# MCU.net
KiCad netlist of a schematic drawn in Altium Designer
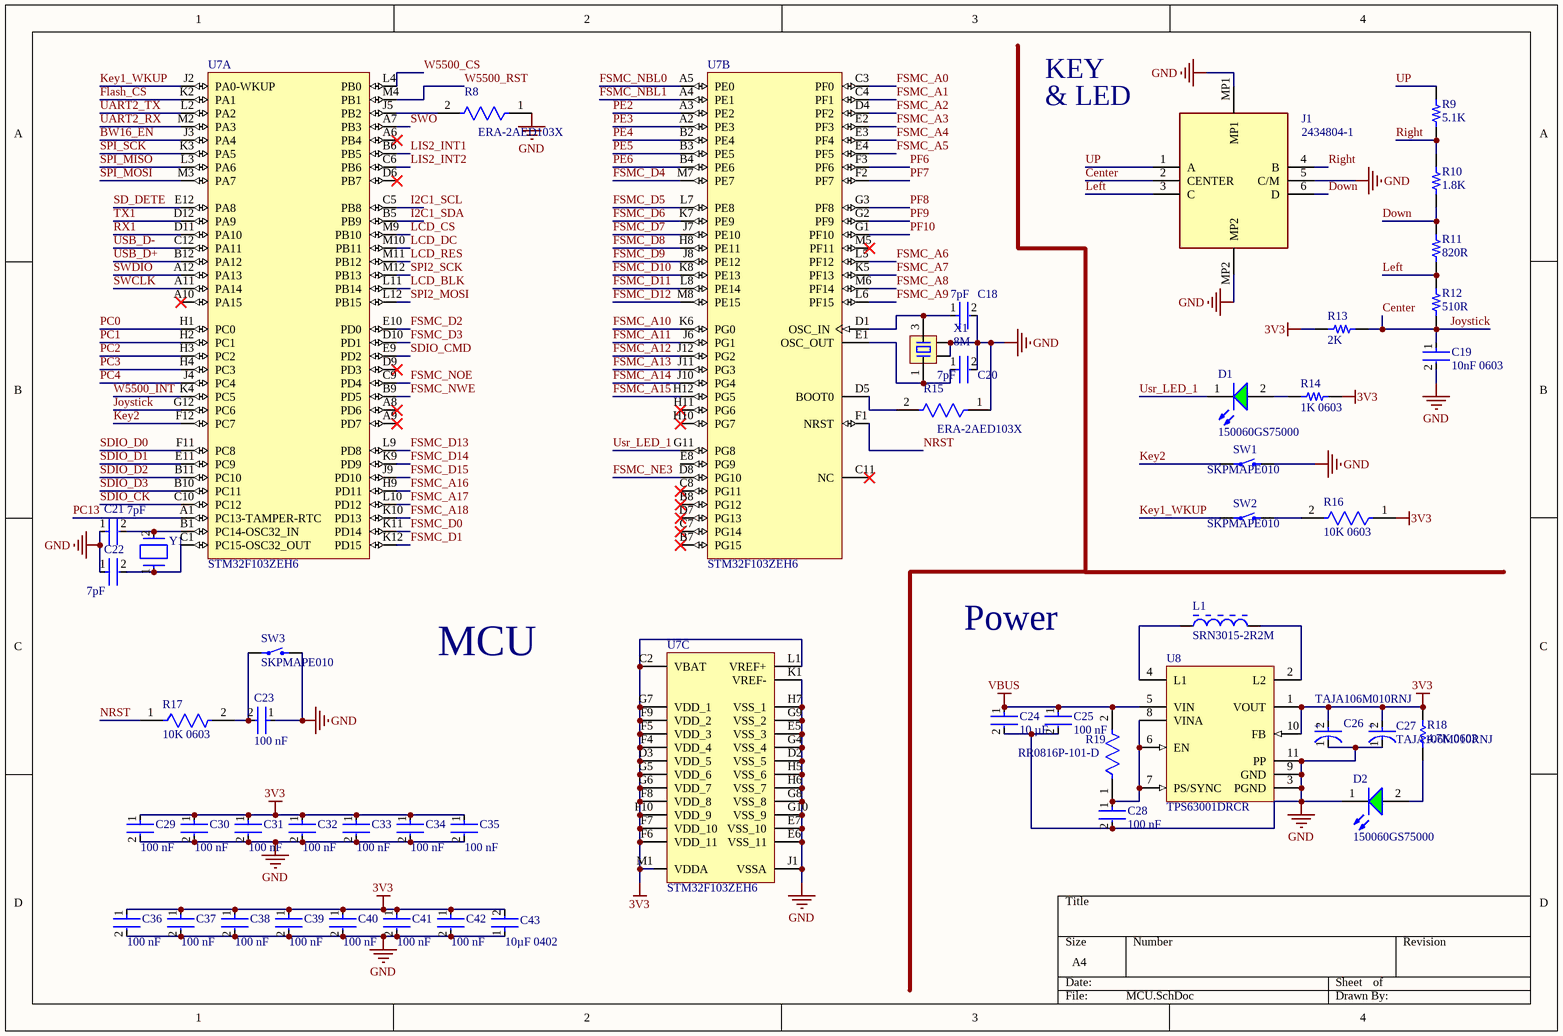
[diagram p0: MCU.SchDoc]

(export (version "E")
  (design (tool "Eeschema 10.0.6"))
  (components
    (comp (ref "C18")
      (value "7pF")
      (footprint "FP-GJM155-0_05-IPC_B")
      (description "Multi-Layer Ceramic Capacitor 7pF C0G  ±0.5pF 0402 Paper T/R")
      (libsource (lib "Altium Content Vault") (part "02cd4be3c70576c341d710602a673aa"))
    )
    (comp (ref "C19")
      (value "10nF 0603")
      (footprint "FP-CC0603-DA-MFG")
      (description "CAP CER 10000PF 50V X7R 0603")
      (fields (field (name "TOLERANCE") "0.1") (field (name "MANUFACTURER PART NUMBER") "CC0603KRX7R9BB103"))
      (libsource (lib "Altium Content Vault") (part "11868f565c42a9108669ba33697ecf6"))
    )
    (comp (ref "C20")
      (value "7pF")
      (footprint "FP-GJM155-0_05-IPC_B")
      (description "Multi-Layer Ceramic Capacitor 7pF C0G  ±0.5pF 0402 Paper T/R")
      (libsource (lib "Altium Content Vault") (part "02cd4be3c70576c341d710602a673aa"))
    )
    (comp (ref "C21")
      (value "7pF")
      (footprint "FP-GJM155-0_05-IPC_B")
      (description "Multi-Layer Ceramic Capacitor 7pF C0G  ±0.5pF 0402 Paper T/R")
      (libsource (lib "Altium Content Vault") (part "02cd4be3c70576c341d710602a673aa"))
    )
    (comp (ref "C22")
      (value "7pF")
      (footprint "FP-GJM155-0_05-IPC_B")
      (description "Multi-Layer Ceramic Capacitor 7pF C0G  ±0.5pF 0402 Paper T/R")
      (libsource (lib "Altium Content Vault") (part "02cd4be3c70576c341d710602a673aa"))
    )
    (comp (ref "C23")
      (value "100 nF")
      (footprint "FP-CL10-IPC_A")
      (description "Cap Ceramic 100nF 100V X7R ±10% Pad SMD 0603 +125°C T/R")
      (fields (field (name "TOLERANCE") "10%"))
      (libsource (lib "Altium Content Vault") (part "b4654b650e69147ec39a6b967a45e02"))
    )
    (comp (ref "C24")
      (value "10 µF")
      (footprint "FP-CL10-IPC_C")
      (description "Cap Ceramic 10uF 25V X5R ±20% Pad SMD 0603 +85°C T/R")
      (fields (field (name "TOLERANCE") "20%"))
      (libsource (lib "Altium Content Vault") (part "b4654b650e69147ec39a6b967a45e02"))
    )
    (comp (ref "C25")
      (value "100 nF")
      (footprint "FP-CL10-IPC_A")
      (description "Cap Ceramic 100nF 100V X7R ±10% Pad SMD 0603 +125°C T/R")
      (fields (field (name "TOLERANCE") "10%"))
      (libsource (lib "Altium Content Vault") (part "b4654b650e69147ec39a6b967a45e02"))
    )
    (comp (ref "C26")
      (value "TAJA106M010RNJ")
      (footprint "FP-TAJA-MFG")
      (description "10uF 10V  ±20% 3Ω 1206  SMD Tantalum Capacitor")
      (fields (field (name "TOLERANCE") "20%") (field (name "VOLTAGE") "10V"))
      (libsource (lib "Altium Content Vault") (part "203bc49f2ac43e59fd269a8c329ed05"))
    )
    (comp (ref "C27")
      (value "TAJA106M010RNJ")
      (footprint "FP-TAJA-MFG")
      (description "10uF 10V  ±20% 3Ω 1206  SMD Tantalum Capacitor")
      (fields (field (name "TOLERANCE") "20%") (field (name "VOLTAGE") "10V"))
      (libsource (lib "Altium Content Vault") (part "203bc49f2ac43e59fd269a8c329ed05"))
    )
    (comp (ref "C28")
      (value "100 nF")
      (footprint "FP-CL10-IPC_A")
      (description "Cap Ceramic 100nF 100V X7R ±10% Pad SMD 0603 +125°C T/R")
      (fields (field (name "TOLERANCE") "10%"))
      (libsource (lib "Altium Content Vault") (part "b4654b650e69147ec39a6b967a45e02"))
    )
    (comp (ref "C29")
      (value "100 nF")
      (footprint "FP-C1005-050-0_05-MFG")
      (description "Multilayer Ceramic Capacitors 100nF ±10% 50V X5R SMD 0402")
      (fields (field (name "VOLTAGE") "50V") (field (name "TOLERANCE") "10%"))
      (libsource (lib "Altium Content Vault") (part "b4654b650e69147ec39a6b967a45e02"))
    )
    (comp (ref "C30")
      (value "100 nF")
      (footprint "FP-C1005-050-0_05-MFG")
      (description "Multilayer Ceramic Capacitors 100nF ±10% 50V X5R SMD 0402")
      (fields (field (name "VOLTAGE") "50V") (field (name "TOLERANCE") "10%"))
      (libsource (lib "Altium Content Vault") (part "b4654b650e69147ec39a6b967a45e02"))
    )
    (comp (ref "C31")
      (value "100 nF")
      (footprint "FP-C1005-050-0_05-MFG")
      (description "Multilayer Ceramic Capacitors 100nF ±10% 50V X5R SMD 0402")
      (fields (field (name "VOLTAGE") "50V") (field (name "TOLERANCE") "10%"))
      (libsource (lib "Altium Content Vault") (part "b4654b650e69147ec39a6b967a45e02"))
    )
    (comp (ref "C32")
      (value "100 nF")
      (footprint "FP-C1005-050-0_05-MFG")
      (description "Multilayer Ceramic Capacitors 100nF ±10% 50V X5R SMD 0402")
      (fields (field (name "VOLTAGE") "50V") (field (name "TOLERANCE") "10%"))
      (libsource (lib "Altium Content Vault") (part "b4654b650e69147ec39a6b967a45e02"))
    )
    (comp (ref "C33")
      (value "100 nF")
      (footprint "FP-C1005-050-0_05-MFG")
      (description "Multilayer Ceramic Capacitors 100nF ±10% 50V X5R SMD 0402")
      (fields (field (name "VOLTAGE") "50V") (field (name "TOLERANCE") "10%"))
      (libsource (lib "Altium Content Vault") (part "b4654b650e69147ec39a6b967a45e02"))
    )
    (comp (ref "C34")
      (value "100 nF")
      (footprint "FP-C1005-050-0_05-MFG")
      (description "Multilayer Ceramic Capacitors 100nF ±10% 50V X5R SMD 0402")
      (fields (field (name "VOLTAGE") "50V") (field (name "TOLERANCE") "10%"))
      (libsource (lib "Altium Content Vault") (part "b4654b650e69147ec39a6b967a45e02"))
    )
    (comp (ref "C35")
      (value "100 nF")
      (footprint "FP-C1005-050-0_05-MFG")
      (description "Multilayer Ceramic Capacitors 100nF ±10% 50V X5R SMD 0402")
      (fields (field (name "VOLTAGE") "50V") (field (name "TOLERANCE") "10%"))
      (libsource (lib "Altium Content Vault") (part "b4654b650e69147ec39a6b967a45e02"))
    )
    (comp (ref "C36")
      (value "100 nF")
      (footprint "FP-C1005-050-0_05-MFG")
      (description "Multilayer Ceramic Capacitors 100nF ±10% 50V X5R SMD 0402")
      (fields (field (name "VOLTAGE") "50V") (field (name "TOLERANCE") "10%"))
      (libsource (lib "Altium Content Vault") (part "b4654b650e69147ec39a6b967a45e02"))
    )
    (comp (ref "C37")
      (value "100 nF")
      (footprint "FP-C1005-050-0_05-MFG")
      (description "Multilayer Ceramic Capacitors 100nF ±10% 50V X5R SMD 0402")
      (fields (field (name "VOLTAGE") "50V") (field (name "TOLERANCE") "10%"))
      (libsource (lib "Altium Content Vault") (part "b4654b650e69147ec39a6b967a45e02"))
    )
    (comp (ref "C38")
      (value "100 nF")
      (footprint "FP-C1005-050-0_05-MFG")
      (description "Multilayer Ceramic Capacitors 100nF ±10% 50V X5R SMD 0402")
      (fields (field (name "VOLTAGE") "50V") (field (name "TOLERANCE") "10%"))
      (libsource (lib "Altium Content Vault") (part "b4654b650e69147ec39a6b967a45e02"))
    )
    (comp (ref "C39")
      (value "100 nF")
      (footprint "FP-C1005-050-0_05-MFG")
      (description "Multilayer Ceramic Capacitors 100nF ±10% 50V X5R SMD 0402")
      (fields (field (name "VOLTAGE") "50V") (field (name "TOLERANCE") "10%"))
      (libsource (lib "Altium Content Vault") (part "b4654b650e69147ec39a6b967a45e02"))
    )
    (comp (ref "C40")
      (value "100 nF")
      (footprint "FP-C1005-050-0_05-MFG")
      (description "Multilayer Ceramic Capacitors 100nF ±10% 50V X5R SMD 0402")
      (fields (field (name "VOLTAGE") "50V") (field (name "TOLERANCE") "10%"))
      (libsource (lib "Altium Content Vault") (part "b4654b650e69147ec39a6b967a45e02"))
    )
    (comp (ref "C41")
      (value "100 nF")
      (footprint "FP-C1005-050-0_05-MFG")
      (description "Multilayer Ceramic Capacitors 100nF ±10% 50V X5R SMD 0402")
      (fields (field (name "VOLTAGE") "50V") (field (name "TOLERANCE") "10%"))
      (libsource (lib "Altium Content Vault") (part "b4654b650e69147ec39a6b967a45e02"))
    )
    (comp (ref "C42")
      (value "100 nF")
      (footprint "FP-C1005-050-0_05-MFG")
      (description "Multilayer Ceramic Capacitors 100nF ±10% 50V X5R SMD 0402")
      (fields (field (name "VOLTAGE") "50V") (field (name "TOLERANCE") "10%"))
      (libsource (lib "Altium Content Vault") (part "b4654b650e69147ec39a6b967a45e02"))
    )
    (comp (ref "C43")
      (value "10µF 0402")
      (footprint "FP-CL05A106MP5NUNC-MFG")
      (description "CAP CER 10UF 10V X5R 0402")
      (fields
        (field (name "OCTOPART") "https://octopart.com/cl05a106mp5nunc-samsung-22457395")
        (field (name "TOLERANCE") "20%")
      )
      (libsource (lib "Altium Content Vault") (part "b4654b650e69147ec39a6b967a45e02"))
    )
    (comp (ref "D1")
      (value "150060GS75000")
      (footprint "WL-SMCW_0603_150060xx75000")
      (libsource (lib "Altium Content Vault") (part "LED_Green_2A-1K"))
    )
    (comp (ref "D2")
      (value "150060GS75000")
      (footprint "WL-SMCW_0603_150060xx75000")
      (libsource (lib "Altium Content Vault") (part "LED_Green_2A-1K"))
    )
    (comp (ref "J1")
      (value "2434804-1")
      (footprint "24348041")
      (fields (field (name "MOUSER PART NUMBER") "655-2434804-1"))
      (libsource (lib "Demo") (part "2434804-1"))
    )
    (comp (ref "L1")
      (value "SRN3015-2R2M")
      (footprint "BOUR-SRN3015-2_V")
      (fields (field (name "MANUFACTURER") "Bourns"))
      (libsource (lib "Altium Content Vault") (part "BOUR-IND-2A"))
    )
    (comp (ref "R8")
      (value "ERA-2AED103X")
      (footprint "FP-ERA2A-IPC_B")
      (description "RES SMD 10K OHM 0.5% 1/16W 0402")
      (fields (field (name "TOLERANCE") "0.5%"))
      (libsource (lib "Altium Content Vault") (part "1029c3af85768c4190bb7ad29bc67b5"))
    )
    (comp (ref "R9")
      (value "5.1K")
      (footprint "5.1K_0603")
      (description "SMT Resistor")
      (libsource (lib "Demo") (part "5.1K_0603"))
    )
    (comp (ref "R10")
      (value "1.8K")
      (footprint "5.1K_0603")
      (description "SMT Resistor")
      (libsource (lib "Demo") (part "5.1K_0603"))
    )
    (comp (ref "R11")
      (value "820R")
      (footprint "5.1K_0603")
      (description "SMT Resistor")
      (libsource (lib "Demo") (part "5.1K_0603"))
    )
    (comp (ref "R12")
      (value "510R")
      (footprint "5.1K_0603")
      (description "SMT Resistor")
      (libsource (lib "Demo") (part "5.1K_0603"))
    )
    (comp (ref "R13")
      (value "2K")
      (footprint "5.1K_0603")
      (description "SMT Resistor")
      (libsource (lib "Demo") (part "5.1K_0603"))
    )
    (comp (ref "R14")
      (value "1K 0603")
      (footprint "4.7R")
      (description "SMT Resistor")
      (libsource (lib "Demo") (part "4.7R 0603"))
    )
    (comp (ref "R15")
      (value "ERA-2AED103X")
      (footprint "FP-ERA2A-IPC_B")
      (description "RES SMD 10K OHM 0.5% 1/16W 0402")
      (fields (field (name "TOLERANCE") "0.5%"))
      (libsource (lib "Altium Content Vault") (part "1029c3af85768c4190bb7ad29bc67b5"))
    )
    (comp (ref "R16")
      (value "10K 0603")
      (footprint "FP-RC0603-0_55-IPC_C")
      (description "RES 10K OHM 1% 1/10W 0603")
      (fields (field (name "TOLERANCE") "1%"))
      (libsource (lib "Altium Content Vault") (part "1029c3af85768c4190bb7ad29bc67b5"))
    )
    (comp (ref "R17")
      (value "10K 0603")
      (footprint "FP-RC0603-0_55-IPC_C")
      (description "RES 10K OHM 1% 1/10W 0603")
      (fields (field (name "TOLERANCE") "1%"))
      (libsource (lib "Altium Content Vault") (part "1029c3af85768c4190bb7ad29bc67b5"))
    )
    (comp (ref "R18")
      (value "4.7K 0603")
      (footprint "RESC1608X55X25LL10T15")
      (description "Chip Resistor, 4.7 KOhm, +/- 1%, 0.1 W, -55 to 155 degC, 0603 (1608 Metric), RoHS, Tape and Reel")
      (fields (field (name "MANUFACTURER") "Yageo") (field (name "TOLERANCE") "1%"))
      (libsource (lib "Altium Content Vault") (part "RES-2"))
    )
    (comp (ref "R19")
      (value "RR0816P-101-D")
      (footprint "FP-RR0816-MFG")
      (description "100Ω ±0.5% 0.0625W 1/16W Chip Resistor 0603 (1608 Metric) Thin Film")
      (fields (field (name "TOLERANCE") "0.5%"))
      (libsource (lib "Altium Content Vault") (part "1029c3af85768c4190bb7ad29bc67b5"))
    )
    (comp (ref "SW1")
      (value "SKPMAPE010")
      (footprint "KEY-SMD_2P-L6.0-W6.0-P6.00")
      (libsource (lib "Demo") (part "SKPMAPE010"))
    )
    (comp (ref "SW2")
      (value "SKPMAPE010")
      (footprint "KEY-SMD_2P-L6.0-W6.0-P6.00")
      (libsource (lib "Demo") (part "SKPMAPE010"))
    )
    (comp (ref "SW3")
      (value "SKPMAPE010")
      (footprint "KEY-SMD_2P-L6.0-W6.0-P6.00")
      (libsource (lib "Demo") (part "SKPMAPE010"))
    )
    (comp (ref "U7")
      (value "STM32F103ZEH6")
      (footprint "STM-LFBGA144")
      (libsource (lib "Altium Content Vault") (part "MC-ARM-STM32F103XC_D_E-GA144"))
    )
    (comp (ref "U8")
      (value "TPS63001DRCR")
      (footprint "DRC0010J_V")
      (fields (field (name "MANUFACTURER") "Texas Instruments"))
      (libsource (lib "Altium Content Vault") (part "TI-TPS63001DRC10-3000X1650TP"))
    )
    (comp (ref "X1")
      (value "8M")
      (footprint "OSC 3225-4P")
      (fields (field (name "版权归属") "源创客"))
      (libsource (lib "Demo") (part "XTAL-4P"))
    )
    (comp (ref "Y1")
      (value "ABS07-120-32.768KHZ-T")
      (footprint "FP-ABS07-120-MFG")
      (description "CRYSTAL 32.7680KHZ 6PF SMD")
      (fields (field (name "TOLERANCE") "20ppm"))
      (libsource (lib "Altium Content Vault") (part "c23a69dc6c9e2f18f2079038eb95dd1"))
    )
  )
  (nets
    (net (code "1") (name "/BW16_EN") (class "Default")
      (node (ref "U7") (pin "J3") (pinfunction "PA4_J3") (pintype "bidirectional"))
    )
    (net (code "2") (name "/Center") (class "Default")
      (node (ref "C19") (pin "1") (pinfunction "1_1") (pintype "passive"))
      (node (ref "J1") (pin "2") (pinfunction "CENTER_2") (pintype "passive"))
      (node (ref "R12") (pin "1") (pinfunction "1_1") (pintype "passive"))
      (node (ref "R13") (pin "1") (pinfunction "1_1") (pintype "passive"))
      (node (ref "U7") (pin "G12") (pinfunction "PC6_G12") (pintype "bidirectional"))
    )
    (net (code "3") (name "/Down") (class "Default")
      (node (ref "J1") (pin "6") (pinfunction "D_6") (pintype "passive"))
      (node (ref "R10") (pin "1") (pinfunction "1_1") (pintype "passive"))
      (node (ref "R11") (pin "2") (pinfunction "2_2") (pintype "passive"))
    )
    (net (code "4") (name "/FSMC_A0") (class "Default")
      (node (ref "U7") (pin "C3") (pinfunction "PF0_C3") (pintype "bidirectional"))
    )
    (net (code "5") (name "/FSMC_A1") (class "Default")
      (node (ref "U7") (pin "C4") (pinfunction "PF1_C4") (pintype "bidirectional"))
    )
    (net (code "6") (name "/FSMC_A2") (class "Default")
      (node (ref "U7") (pin "D4") (pinfunction "PF2_D4") (pintype "bidirectional"))
    )
    (net (code "7") (name "/FSMC_A3") (class "Default")
      (node (ref "U7") (pin "E2") (pinfunction "PF3_E2") (pintype "bidirectional"))
    )
    (net (code "8") (name "/FSMC_A4") (class "Default")
      (node (ref "U7") (pin "E3") (pinfunction "PF4_E3") (pintype "bidirectional"))
    )
    (net (code "9") (name "/FSMC_A5") (class "Default")
      (node (ref "U7") (pin "E4") (pinfunction "PF5_E4") (pintype "bidirectional"))
    )
    (net (code "10") (name "/FSMC_A6") (class "Default")
      (node (ref "U7") (pin "L5") (pinfunction "PF12_L5") (pintype "bidirectional"))
    )
    (net (code "11") (name "/FSMC_A7") (class "Default")
      (node (ref "U7") (pin "K5") (pinfunction "PF13_K5") (pintype "bidirectional"))
    )
    (net (code "12") (name "/FSMC_A8") (class "Default")
      (node (ref "U7") (pin "M6") (pinfunction "PF14_M6") (pintype "bidirectional"))
    )
    (net (code "13") (name "/FSMC_A9") (class "Default")
      (node (ref "U7") (pin "L6") (pinfunction "PF15_L6") (pintype "bidirectional"))
    )
    (net (code "14") (name "/FSMC_A10") (class "Default")
      (node (ref "U7") (pin "K6") (pinfunction "PG0_K6") (pintype "bidirectional"))
    )
    (net (code "15") (name "/FSMC_A11") (class "Default")
      (node (ref "U7") (pin "J6") (pinfunction "PG1_J6") (pintype "bidirectional"))
    )
    (net (code "16") (name "/FSMC_A12") (class "Default")
      (node (ref "U7") (pin "J12") (pinfunction "PG2_J12") (pintype "bidirectional"))
    )
    (net (code "17") (name "/FSMC_A13") (class "Default")
      (node (ref "U7") (pin "J11") (pinfunction "PG3_J11") (pintype "bidirectional"))
    )
    (net (code "18") (name "/FSMC_A14") (class "Default")
      (node (ref "U7") (pin "J10") (pinfunction "PG4_J10") (pintype "bidirectional"))
    )
    (net (code "19") (name "/FSMC_A15") (class "Default")
      (node (ref "U7") (pin "H12") (pinfunction "PG5_H12") (pintype "bidirectional"))
    )
    (net (code "20") (name "/FSMC_A16") (class "Default")
      (node (ref "U7") (pin "H9") (pinfunction "PD11_H9") (pintype "bidirectional"))
    )
    (net (code "21") (name "/FSMC_A17") (class "Default")
      (node (ref "U7") (pin "L10") (pinfunction "PD12_L10") (pintype "bidirectional"))
    )
    (net (code "22") (name "/FSMC_A18") (class "Default")
      (node (ref "U7") (pin "K10") (pinfunction "PD13_K10") (pintype "bidirectional"))
    )
    (net (code "23") (name "/FSMC_D0") (class "Default")
      (node (ref "U7") (pin "K11") (pinfunction "PD14_K11") (pintype "bidirectional"))
    )
    (net (code "24") (name "/FSMC_D1") (class "Default")
      (node (ref "U7") (pin "K12") (pinfunction "PD15_K12") (pintype "bidirectional"))
    )
    (net (code "25") (name "/FSMC_D2") (class "Default")
      (node (ref "U7") (pin "E10") (pinfunction "PD0_E10") (pintype "bidirectional"))
    )
    (net (code "26") (name "/FSMC_D3") (class "Default")
      (node (ref "U7") (pin "D10") (pinfunction "PD1_D10") (pintype "bidirectional"))
    )
    (net (code "27") (name "/FSMC_D4") (class "Default")
      (node (ref "U7") (pin "M7") (pinfunction "PE7_M7") (pintype "bidirectional"))
    )
    (net (code "28") (name "/FSMC_D5") (class "Default")
      (node (ref "U7") (pin "L7") (pinfunction "PE8_L7") (pintype "bidirectional"))
    )
    (net (code "29") (name "/FSMC_D6") (class "Default")
      (node (ref "U7") (pin "K7") (pinfunction "PE9_K7") (pintype "bidirectional"))
    )
    (net (code "30") (name "/FSMC_D7") (class "Default")
      (node (ref "U7") (pin "J7") (pinfunction "PE10_J7") (pintype "bidirectional"))
    )
    (net (code "31") (name "/FSMC_D8") (class "Default")
      (node (ref "U7") (pin "H8") (pinfunction "PE11_H8") (pintype "bidirectional"))
    )
    (net (code "32") (name "/FSMC_D9") (class "Default")
      (node (ref "U7") (pin "J8") (pinfunction "PE12_J8") (pintype "bidirectional"))
    )
    (net (code "33") (name "/FSMC_D10") (class "Default")
      (node (ref "U7") (pin "K8") (pinfunction "PE13_K8") (pintype "bidirectional"))
    )
    (net (code "34") (name "/FSMC_D11") (class "Default")
      (node (ref "U7") (pin "L8") (pinfunction "PE14_L8") (pintype "bidirectional"))
    )
    (net (code "35") (name "/FSMC_D12") (class "Default")
      (node (ref "U7") (pin "M8") (pinfunction "PE15_M8") (pintype "bidirectional"))
    )
    (net (code "36") (name "/FSMC_D13") (class "Default")
      (node (ref "U7") (pin "L9") (pinfunction "PD8_L9") (pintype "bidirectional"))
    )
    (net (code "37") (name "/FSMC_D14") (class "Default")
      (node (ref "U7") (pin "K9") (pinfunction "PD9_K9") (pintype "bidirectional"))
    )
    (net (code "38") (name "/FSMC_D15") (class "Default")
      (node (ref "U7") (pin "J9") (pinfunction "PD10_J9") (pintype "bidirectional"))
    )
    (net (code "39") (name "/FSMC_NBL0") (class "Default")
      (node (ref "U7") (pin "A5") (pinfunction "PE0_A5") (pintype "bidirectional"))
    )
    (net (code "40") (name "/FSMC_NBL1") (class "Default")
      (node (ref "U7") (pin "A4") (pinfunction "PE1_A4") (pintype "bidirectional"))
    )
    (net (code "41") (name "/FSMC_NE3") (class "Default")
      (node (ref "U7") (pin "D8") (pinfunction "PG10_D8") (pintype "bidirectional"))
    )
    (net (code "42") (name "/FSMC_NOE") (class "Default")
      (node (ref "U7") (pin "C9") (pinfunction "PD4_C9") (pintype "bidirectional"))
    )
    (net (code "43") (name "/FSMC_NWE") (class "Default")
      (node (ref "U7") (pin "B9") (pinfunction "PD5_B9") (pintype "bidirectional"))
    )
    (net (code "44") (name "/Flash_CS") (class "Default")
      (node (ref "U7") (pin "K2") (pinfunction "PA1_K2") (pintype "bidirectional"))
    )
    (net (code "45") (name "/I2C1_SCL") (class "Default")
      (node (ref "U7") (pin "C5") (pinfunction "PB8_C5") (pintype "bidirectional"))
    )
    (net (code "46") (name "/I2C1_SDA") (class "Default")
      (node (ref "U7") (pin "B5") (pinfunction "PB9_B5") (pintype "bidirectional"))
    )
    (net (code "47") (name "/Key1_WKUP") (class "Default")
      (node (ref "SW2") (pin "1") (pinfunction "1_1") (pintype "passive"))
      (node (ref "U7") (pin "J2") (pinfunction "PA0-WKUP_J2") (pintype "bidirectional"))
    )
    (net (code "48") (name "/Key2") (class "Default")
      (node (ref "SW1") (pin "1") (pinfunction "1_1") (pintype "passive"))
      (node (ref "U7") (pin "F12") (pinfunction "PC7_F12") (pintype "bidirectional"))
    )
    (net (code "49") (name "/LCD_BLK") (class "Default")
      (node (ref "U7") (pin "L11") (pinfunction "PB14_L11") (pintype "bidirectional"))
    )
    (net (code "50") (name "/LCD_CS") (class "Default")
      (node (ref "U7") (pin "M9") (pinfunction "PB10_M9") (pintype "bidirectional"))
    )
    (net (code "51") (name "/LCD_DC") (class "Default")
      (node (ref "U7") (pin "M10") (pinfunction "PB11_M10") (pintype "bidirectional"))
    )
    (net (code "52") (name "/LCD_RES") (class "Default")
      (node (ref "U7") (pin "M11") (pinfunction "PB12_M11") (pintype "bidirectional"))
    )
    (net (code "53") (name "/LIS2_INT1") (class "Default")
      (node (ref "U7") (pin "B6") (pinfunction "PB5_B6") (pintype "bidirectional"))
    )
    (net (code "54") (name "/LIS2_INT2") (class "Default")
      (node (ref "U7") (pin "C6") (pinfunction "PB6_C6") (pintype "bidirectional"))
    )
    (net (code "55") (name "/Left") (class "Default")
      (node (ref "J1") (pin "3") (pinfunction "C_3") (pintype "passive"))
      (node (ref "R11") (pin "1") (pinfunction "1_1") (pintype "passive"))
      (node (ref "R12") (pin "2") (pinfunction "2_2") (pintype "passive"))
    )
    (net (code "56") (name "/NRST") (class "Default")
      (node (ref "R17") (pin "1") (pinfunction "1_1") (pintype "passive"))
      (node (ref "U7") (pin "F1") (pinfunction "NRST_F1") (pintype "bidirectional"))
    )
    (net (code "57") (name "/PC0") (class "Default")
      (node (ref "U7") (pin "H1") (pinfunction "PC0_H1") (pintype "bidirectional"))
    )
    (net (code "58") (name "/PC1") (class "Default")
      (node (ref "U7") (pin "H2") (pinfunction "PC1_H2") (pintype "bidirectional"))
    )
    (net (code "59") (name "/PC2") (class "Default")
      (node (ref "U7") (pin "H3") (pinfunction "PC2_H3") (pintype "bidirectional"))
    )
    (net (code "60") (name "/PC3") (class "Default")
      (node (ref "U7") (pin "H4") (pinfunction "PC3_H4") (pintype "bidirectional"))
    )
    (net (code "61") (name "/PC4") (class "Default")
      (node (ref "U7") (pin "J4") (pinfunction "PC4_J4") (pintype "bidirectional"))
    )
    (net (code "62") (name "/PC13") (class "Default")
      (node (ref "U7") (pin "A1") (pinfunction "PC13-TAMPER-RTC_A1") (pintype "bidirectional"))
    )
    (net (code "63") (name "/PE2") (class "Default")
      (node (ref "U7") (pin "A3") (pinfunction "PE2_A3") (pintype "bidirectional"))
    )
    (net (code "64") (name "/PE3") (class "Default")
      (node (ref "U7") (pin "A2") (pinfunction "PE3_A2") (pintype "bidirectional"))
    )
    (net (code "65") (name "/PE4") (class "Default")
      (node (ref "U7") (pin "B2") (pinfunction "PE4_B2") (pintype "bidirectional"))
    )
    (net (code "66") (name "/PE5") (class "Default")
      (node (ref "U7") (pin "B3") (pinfunction "PE5_B3") (pintype "bidirectional"))
    )
    (net (code "67") (name "/PE6") (class "Default")
      (node (ref "U7") (pin "B4") (pinfunction "PE6_B4") (pintype "bidirectional"))
    )
    (net (code "68") (name "/PF6") (class "Default")
      (node (ref "U7") (pin "F3") (pinfunction "PF6_F3") (pintype "bidirectional"))
    )
    (net (code "69") (name "/PF7") (class "Default")
      (node (ref "U7") (pin "F2") (pinfunction "PF7_F2") (pintype "bidirectional"))
    )
    (net (code "70") (name "/PF8") (class "Default")
      (node (ref "U7") (pin "G3") (pinfunction "PF8_G3") (pintype "bidirectional"))
    )
    (net (code "71") (name "/PF9") (class "Default")
      (node (ref "U7") (pin "G2") (pinfunction "PF9_G2") (pintype "bidirectional"))
    )
    (net (code "72") (name "/PF10") (class "Default")
      (node (ref "U7") (pin "G1") (pinfunction "PF10_G1") (pintype "bidirectional"))
    )
    (net (code "73") (name "/RX1") (class "Default")
      (node (ref "U7") (pin "D11") (pinfunction "PA10_D11") (pintype "bidirectional"))
    )
    (net (code "74") (name "/Right") (class "Default")
      (node (ref "J1") (pin "4") (pinfunction "B_4") (pintype "passive"))
      (node (ref "R10") (pin "2") (pinfunction "2_2") (pintype "passive"))
      (node (ref "R9") (pin "1") (pinfunction "1_1") (pintype "passive"))
    )
    (net (code "75") (name "/SDIO_CK") (class "Default")
      (node (ref "U7") (pin "C10") (pinfunction "PC12_C10") (pintype "bidirectional"))
    )
    (net (code "76") (name "/SDIO_CMD") (class "Default")
      (node (ref "U7") (pin "E9") (pinfunction "PD2_E9") (pintype "bidirectional"))
    )
    (net (code "77") (name "/SDIO_D0") (class "Default")
      (node (ref "U7") (pin "F11") (pinfunction "PC8_F11") (pintype "bidirectional"))
    )
    (net (code "78") (name "/SDIO_D1") (class "Default")
      (node (ref "U7") (pin "E11") (pinfunction "PC9_E11") (pintype "bidirectional"))
    )
    (net (code "79") (name "/SDIO_D2") (class "Default")
      (node (ref "U7") (pin "B11") (pinfunction "PC10_B11") (pintype "bidirectional"))
    )
    (net (code "80") (name "/SDIO_D3") (class "Default")
      (node (ref "U7") (pin "B10") (pinfunction "PC11_B10") (pintype "bidirectional"))
    )
    (net (code "81") (name "/SD_DETE") (class "Default")
      (node (ref "U7") (pin "E12") (pinfunction "PA8_E12") (pintype "bidirectional"))
    )
    (net (code "82") (name "/SPI2_MOSI") (class "Default")
      (node (ref "U7") (pin "L12") (pinfunction "PB15_L12") (pintype "bidirectional"))
    )
    (net (code "83") (name "/SPI2_SCK") (class "Default")
      (node (ref "U7") (pin "M12") (pinfunction "PB13_M12") (pintype "bidirectional"))
    )
    (net (code "84") (name "/SPI_MISO") (class "Default")
      (node (ref "U7") (pin "L3") (pinfunction "PA6_L3") (pintype "bidirectional"))
    )
    (net (code "85") (name "/SPI_MOSI") (class "Default")
      (node (ref "U7") (pin "M3") (pinfunction "PA7_M3") (pintype "bidirectional"))
    )
    (net (code "86") (name "/SPI_SCK") (class "Default")
      (node (ref "U7") (pin "K3") (pinfunction "PA5_K3") (pintype "bidirectional"))
    )
    (net (code "87") (name "/SWCLK") (class "Default")
      (node (ref "U7") (pin "A11") (pinfunction "PA14_A11") (pintype "bidirectional"))
    )
    (net (code "88") (name "/SWDIO") (class "Default")
      (node (ref "U7") (pin "A12") (pinfunction "PA13_A12") (pintype "bidirectional"))
    )
    (net (code "89") (name "/SWO") (class "Default")
      (node (ref "U7") (pin "A7") (pinfunction "PB3_A7") (pintype "bidirectional"))
    )
    (net (code "90") (name "/TX1") (class "Default")
      (node (ref "U7") (pin "D12") (pinfunction "PA9_D12") (pintype "bidirectional"))
    )
    (net (code "91") (name "/UART2_RX") (class "Default")
      (node (ref "U7") (pin "M2") (pinfunction "PA3_M2") (pintype "bidirectional"))
    )
    (net (code "92") (name "/UART2_TX") (class "Default")
      (node (ref "U7") (pin "L2") (pinfunction "PA2_L2") (pintype "bidirectional"))
    )
    (net (code "93") (name "/UP") (class "Default")
      (node (ref "J1") (pin "1") (pinfunction "A_1") (pintype "passive"))
      (node (ref "R9") (pin "2") (pinfunction "2_2") (pintype "passive"))
    )
    (net (code "94") (name "/USB_D+") (class "Default")
      (node (ref "U7") (pin "B12") (pinfunction "PA12_B12") (pintype "bidirectional"))
    )
    (net (code "95") (name "/USB_D-") (class "Default")
      (node (ref "U7") (pin "C12") (pinfunction "PA11_C12") (pintype "bidirectional"))
    )
    (net (code "96") (name "/Usr_LED_1") (class "Default")
      (node (ref "D1") (pin "1") (pinfunction "K_1") (pintype "passive"))
      (node (ref "U7") (pin "G11") (pinfunction "PG8_G11") (pintype "bidirectional"))
    )
    (net (code "97") (name "/W5500_CS") (class "Default")
      (node (ref "U7") (pin "L4") (pinfunction "PB0_L4") (pintype "bidirectional"))
    )
    (net (code "98") (name "/W5500_INT") (class "Default")
      (node (ref "U7") (pin "K4") (pinfunction "PC5_K4") (pintype "bidirectional"))
    )
    (net (code "99") (name "/W5500_RST") (class "Default")
      (node (ref "U7") (pin "M4") (pinfunction "PB1_M4") (pintype "bidirectional"))
    )
    (net (code "100") (name "3V3") (class "Default")
      (node (ref "C26") (pin "2") (pinfunction "A_2") (pintype "passive"))
      (node (ref "C27") (pin "2") (pinfunction "A_2") (pintype "passive"))
      (node (ref "C29") (pin "1") (pinfunction "1_1") (pintype "passive"))
      (node (ref "C30") (pin "1") (pinfunction "1_1") (pintype "passive"))
      (node (ref "C31") (pin "1") (pinfunction "1_1") (pintype "passive"))
      (node (ref "C32") (pin "1") (pinfunction "1_1") (pintype "passive"))
      (node (ref "C33") (pin "1") (pinfunction "1_1") (pintype "passive"))
      (node (ref "C34") (pin "1") (pinfunction "1_1") (pintype "passive"))
      (node (ref "C35") (pin "1") (pinfunction "1_1") (pintype "passive"))
      (node (ref "C36") (pin "1") (pinfunction "1_1") (pintype "passive"))
      (node (ref "C37") (pin "1") (pinfunction "1_1") (pintype "passive"))
      (node (ref "C38") (pin "1") (pinfunction "1_1") (pintype "passive"))
      (node (ref "C39") (pin "1") (pinfunction "1_1") (pintype "passive"))
      (node (ref "C40") (pin "1") (pinfunction "1_1") (pintype "passive"))
      (node (ref "C41") (pin "1") (pinfunction "1_1") (pintype "passive"))
      (node (ref "C42") (pin "1") (pinfunction "1_1") (pintype "passive"))
      (node (ref "C43") (pin "2") (pinfunction "2_2") (pintype "passive"))
      (node (ref "R13") (pin "2") (pinfunction "2_2") (pintype "passive"))
      (node (ref "R14") (pin "2") (pinfunction "2_2") (pintype "passive"))
      (node (ref "R16") (pin "1") (pinfunction "1_1") (pintype "passive"))
      (node (ref "R18") (pin "2") (pinfunction "2_2") (pintype "passive"))
      (node (ref "U7") (pin "C2") (pinfunction "VBAT_C2") (pintype "power_in"))
      (node (ref "U7") (pin "D3") (pinfunction "VDD_5_D3") (pintype "power_in"))
      (node (ref "U7") (pin "F10") (pinfunction "VDD_9_F10") (pintype "power_in"))
      (node (ref "U7") (pin "F4") (pinfunction "VDD_4_F4") (pintype "power_in"))
      (node (ref "U7") (pin "F5") (pinfunction "VDD_3_F5") (pintype "power_in"))
      (node (ref "U7") (pin "F6") (pinfunction "VDD_11_F6") (pintype "power_in"))
      (node (ref "U7") (pin "F7") (pinfunction "VDD_10_F7") (pintype "power_in"))
      (node (ref "U7") (pin "F8") (pinfunction "VDD_8_F8") (pintype "power_in"))
      (node (ref "U7") (pin "F9") (pinfunction "VDD_2_F9") (pintype "power_in"))
      (node (ref "U7") (pin "G5") (pinfunction "VDD_6_G5") (pintype "power_in"))
      (node (ref "U7") (pin "G6") (pinfunction "VDD_7_G6") (pintype "power_in"))
      (node (ref "U7") (pin "G7") (pinfunction "VDD_1_G7") (pintype "power_in"))
      (node (ref "U7") (pin "L1") (pinfunction "VREF+_L1") (pintype "power_in"))
      (node (ref "U7") (pin "M1") (pinfunction "VDDA_M1") (pintype "power_in"))
      (node (ref "U8") (pin "1") (pinfunction "VOUT_1") (pintype "power_in"))
      (node (ref "U8") (pin "10") (pinfunction "FB_10") (pintype "input"))
    )
    (net (code "101") (name "GND") (class "Default")
      (node (ref "C18") (pin "2") (pinfunction "2_2") (pintype "passive"))
      (node (ref "C19") (pin "2") (pinfunction "2_2") (pintype "passive"))
      (node (ref "C20") (pin "2") (pinfunction "2_2") (pintype "passive"))
      (node (ref "C21") (pin "1") (pinfunction "1_1") (pintype "passive"))
      (node (ref "C22") (pin "1") (pinfunction "1_1") (pintype "passive"))
      (node (ref "C23") (pin "1") (pinfunction "1_1") (pintype "passive"))
      (node (ref "C24") (pin "2") (pinfunction "2_2") (pintype "passive"))
      (node (ref "C25") (pin "2") (pinfunction "2_2") (pintype "passive"))
      (node (ref "C26") (pin "1") (pinfunction "C_1") (pintype "passive"))
      (node (ref "C27") (pin "1") (pinfunction "C_1") (pintype "passive"))
      (node (ref "C28") (pin "2") (pinfunction "2_2") (pintype "passive"))
      (node (ref "C29") (pin "2") (pinfunction "2_2") (pintype "passive"))
      (node (ref "C30") (pin "2") (pinfunction "2_2") (pintype "passive"))
      (node (ref "C31") (pin "2") (pinfunction "2_2") (pintype "passive"))
      (node (ref "C32") (pin "2") (pinfunction "2_2") (pintype "passive"))
      (node (ref "C33") (pin "2") (pinfunction "2_2") (pintype "passive"))
      (node (ref "C34") (pin "2") (pinfunction "2_2") (pintype "passive"))
      (node (ref "C35") (pin "2") (pinfunction "2_2") (pintype "passive"))
      (node (ref "C36") (pin "2") (pinfunction "2_2") (pintype "passive"))
      (node (ref "C37") (pin "2") (pinfunction "2_2") (pintype "passive"))
      (node (ref "C38") (pin "2") (pinfunction "2_2") (pintype "passive"))
      (node (ref "C39") (pin "2") (pinfunction "2_2") (pintype "passive"))
      (node (ref "C40") (pin "2") (pinfunction "2_2") (pintype "passive"))
      (node (ref "C41") (pin "2") (pinfunction "2_2") (pintype "passive"))
      (node (ref "C42") (pin "2") (pinfunction "2_2") (pintype "passive"))
      (node (ref "C43") (pin "1") (pinfunction "1_1") (pintype "passive"))
      (node (ref "D2") (pin "1") (pinfunction "K_1") (pintype "passive"))
      (node (ref "J1") (pin "5") (pinfunction "C/M_5") (pintype "passive"))
      (node (ref "J1") (pin "MP1") (pinfunction "MP1_MP1") (pintype "passive"))
      (node (ref "J1") (pin "MP2") (pinfunction "MP2_MP2") (pintype "passive"))
      (node (ref "R15") (pin "1") (pinfunction "1_1") (pintype "passive"))
      (node (ref "R8") (pin "1") (pinfunction "1_1") (pintype "passive"))
      (node (ref "SW1") (pin "2") (pinfunction "2_2") (pintype "passive"))
      (node (ref "SW3") (pin "2") (pinfunction "2_2") (pintype "passive"))
      (node (ref "U7") (pin "D2") (pinfunction "VSS_5_D2") (pintype "power_in"))
      (node (ref "U7") (pin "E5") (pinfunction "VSS_3_E5") (pintype "power_in"))
      (node (ref "U7") (pin "E6") (pinfunction "VSS_11_E6") (pintype "power_in"))
      (node (ref "U7") (pin "E7") (pinfunction "VSS_10_E7") (pintype "power_in"))
      (node (ref "U7") (pin "G10") (pinfunction "VSS_9_G10") (pintype "power_in"))
      (node (ref "U7") (pin "G4") (pinfunction "VSS_4_G4") (pintype "power_in"))
      (node (ref "U7") (pin "G8") (pinfunction "VSS_8_G8") (pintype "power_in"))
      (node (ref "U7") (pin "G9") (pinfunction "VSS_2_G9") (pintype "power_in"))
      (node (ref "U7") (pin "H5") (pinfunction "VSS_6_H5") (pintype "power_in"))
      (node (ref "U7") (pin "H6") (pinfunction "VSS_7_H6") (pintype "power_in"))
      (node (ref "U7") (pin "H7") (pinfunction "VSS_1_H7") (pintype "power_in"))
      (node (ref "U7") (pin "J1") (pinfunction "VSSA_J1") (pintype "power_in"))
      (node (ref "U7") (pin "K1") (pinfunction "VREF-_K1") (pintype "power_in"))
      (node (ref "U8") (pin "11") (pinfunction "PP_11") (pintype "power_in"))
      (node (ref "U8") (pin "3") (pinfunction "PGND_3") (pintype "power_in"))
      (node (ref "U8") (pin "9") (pinfunction "GND_9") (pintype "power_in"))
      (node (ref "X1") (pin "2") (pinfunction "2_2") (pintype "passive"))
      (node (ref "X1") (pin "4") (pinfunction "4_4") (pintype "passive"))
    )
    (net (code "102") (name "Net-(C23-Pad2)") (class "Default")
      (node (ref "C23") (pin "2") (pinfunction "2_2") (pintype "passive"))
      (node (ref "R17") (pin "2") (pinfunction "2_2") (pintype "passive"))
      (node (ref "SW3") (pin "1") (pinfunction "1_1") (pintype "passive"))
    )
    (net (code "103") (name "Net-(D1-A)") (class "Default")
      (node (ref "D1") (pin "2") (pinfunction "A_2") (pintype "passive"))
      (node (ref "R14") (pin "1") (pinfunction "1_1") (pintype "passive"))
    )
    (net (code "104") (name "Net-(D2-A)") (class "Default")
      (node (ref "D2") (pin "2") (pinfunction "A_2") (pintype "passive"))
      (node (ref "R18") (pin "1") (pinfunction "1_1") (pintype "passive"))
    )
    (net (code "105") (name "Net-(R16-Pad2)") (class "Default")
      (node (ref "R16") (pin "2") (pinfunction "2_2") (pintype "passive"))
      (node (ref "SW2") (pin "2") (pinfunction "2_2") (pintype "passive"))
    )
    (net (code "106") (name "Net-(U7A-PB2)") (class "Default")
      (node (ref "R8") (pin "2") (pinfunction "2_2") (pintype "passive"))
      (node (ref "U7") (pin "J5") (pinfunction "PB2_J5") (pintype "bidirectional"))
    )
    (net (code "107") (name "Net-(U7A-PC14-OSC32_IN)") (class "Default")
      (node (ref "C21") (pin "2") (pinfunction "2_2") (pintype "passive"))
      (node (ref "U7") (pin "B1") (pinfunction "PC14-OSC32_IN_B1") (pintype "bidirectional"))
      (node (ref "Y1") (pin "2") (pinfunction "2_2") (pintype "passive"))
    )
    (net (code "108") (name "Net-(U7A-PC15-OSC32_OUT)") (class "Default")
      (node (ref "C22") (pin "2") (pinfunction "2_2") (pintype "passive"))
      (node (ref "U7") (pin "C1") (pinfunction "PC15-OSC32_OUT_C1") (pintype "bidirectional"))
      (node (ref "Y1") (pin "1") (pinfunction "1_1") (pintype "passive"))
    )
    (net (code "109") (name "Net-(U7B-BOOT0)") (class "Default")
      (node (ref "R15") (pin "2") (pinfunction "2_2") (pintype "passive"))
      (node (ref "U7") (pin "D5") (pinfunction "BOOT0_D5") (pintype "input"))
    )
    (net (code "110") (name "Net-(U7B-OSC_IN)") (class "Default")
      (node (ref "C18") (pin "1") (pinfunction "1_1") (pintype "passive"))
      (node (ref "U7") (pin "D1") (pinfunction "OSC_IN_D1") (pintype "input"))
      (node (ref "X1") (pin "3") (pinfunction "3_3") (pintype "passive"))
    )
    (net (code "111") (name "Net-(U7B-OSC_OUT)") (class "Default")
      (node (ref "C20") (pin "1") (pinfunction "1_1") (pintype "passive"))
      (node (ref "U7") (pin "E1") (pinfunction "OSC_OUT_E1") (pintype "passive"))
      (node (ref "X1") (pin "1") (pinfunction "1_1") (pintype "passive"))
    )
    (net (code "112") (name "Net-(U8-EN)") (class "Default")
      (node (ref "C28") (pin "1") (pinfunction "1_1") (pintype "passive"))
      (node (ref "R19") (pin "1") (pinfunction "1_1") (pintype "passive"))
      (node (ref "U8") (pin "6") (pinfunction "EN_6") (pintype "input"))
      (node (ref "U8") (pin "7") (pinfunction "PS/SYNC_7") (pintype "input"))
      (node (ref "U8") (pin "8") (pinfunction "VINA_8") (pintype "power_in"))
    )
    (net (code "113") (name "Net-(U8-L1)") (class "Default")
      (node (ref "L1") (pin "1") (pinfunction "1_1") (pintype "passive"))
      (node (ref "U8") (pin "4") (pinfunction "L1_4") (pintype "passive"))
    )
    (net (code "114") (name "Net-(U8-L2)") (class "Default")
      (node (ref "L1") (pin "2") (pinfunction "2_2") (pintype "passive"))
      (node (ref "U8") (pin "2") (pinfunction "L2_2") (pintype "passive"))
    )
    (net (code "115") (name "VBUS") (class "Default")
      (node (ref "C24") (pin "1") (pinfunction "1_1") (pintype "passive"))
      (node (ref "C25") (pin "1") (pinfunction "1_1") (pintype "passive"))
      (node (ref "R19") (pin "2") (pinfunction "2_2") (pintype "passive"))
      (node (ref "U8") (pin "5") (pinfunction "VIN_5") (pintype "power_in"))
    )
    (net (code "116") (name "unconnected-(U7A-PA15-PadA10)") (class "Default")
      (node (ref "U7") (pin "A10") (pinfunction "PA15_A10") (pintype "bidirectional+no_connect"))
    )
    (net (code "117") (name "unconnected-(U7A-PB4-PadA6)") (class "Default")
      (node (ref "U7") (pin "A6") (pinfunction "PB4_A6") (pintype "bidirectional+no_connect"))
    )
    (net (code "118") (name "unconnected-(U7A-PB7-PadD6)") (class "Default")
      (node (ref "U7") (pin "D6") (pinfunction "PB7_D6") (pintype "bidirectional+no_connect"))
    )
    (net (code "119") (name "unconnected-(U7A-PD3-PadD9)") (class "Default")
      (node (ref "U7") (pin "D9") (pinfunction "PD3_D9") (pintype "bidirectional+no_connect"))
    )
    (net (code "120") (name "unconnected-(U7A-PD6-PadA8)") (class "Default")
      (node (ref "U7") (pin "A8") (pinfunction "PD6_A8") (pintype "bidirectional+no_connect"))
    )
    (net (code "121") (name "unconnected-(U7A-PD7-PadA9)") (class "Default")
      (node (ref "U7") (pin "A9") (pinfunction "PD7_A9") (pintype "bidirectional+no_connect"))
    )
    (net (code "122") (name "unconnected-(U7B-NC-PadC11)") (class "Default")
      (node (ref "U7") (pin "C11") (pinfunction "NC_C11") (pintype "passive+no_connect"))
    )
    (net (code "123") (name "unconnected-(U7B-PF11-PadM5)") (class "Default")
      (node (ref "U7") (pin "M5") (pinfunction "PF11_M5") (pintype "bidirectional+no_connect"))
    )
    (net (code "124") (name "unconnected-(U7B-PG6-PadH11)") (class "Default")
      (node (ref "U7") (pin "H11") (pinfunction "PG6_H11") (pintype "bidirectional+no_connect"))
    )
    (net (code "125") (name "unconnected-(U7B-PG7-PadH10)") (class "Default")
      (node (ref "U7") (pin "H10") (pinfunction "PG7_H10") (pintype "bidirectional+no_connect"))
    )
    (net (code "126") (name "unconnected-(U7B-PG9-PadE8)") (class "Default")
      (node (ref "U7") (pin "E8") (pinfunction "PG9_E8") (pintype "bidirectional"))
    )
    (net (code "127") (name "unconnected-(U7B-PG11-PadC8)") (class "Default")
      (node (ref "U7") (pin "C8") (pinfunction "PG11_C8") (pintype "bidirectional+no_connect"))
    )
    (net (code "128") (name "unconnected-(U7B-PG12-PadB8)") (class "Default")
      (node (ref "U7") (pin "B8") (pinfunction "PG12_B8") (pintype "bidirectional+no_connect"))
    )
    (net (code "129") (name "unconnected-(U7B-PG13-PadD7)") (class "Default")
      (node (ref "U7") (pin "D7") (pinfunction "PG13_D7") (pintype "bidirectional+no_connect"))
    )
    (net (code "130") (name "unconnected-(U7B-PG14-PadC7)") (class "Default")
      (node (ref "U7") (pin "C7") (pinfunction "PG14_C7") (pintype "bidirectional+no_connect"))
    )
    (net (code "131") (name "unconnected-(U7B-PG15-PadB7)") (class "Default")
      (node (ref "U7") (pin "B7") (pinfunction "PG15_B7") (pintype "bidirectional+no_connect"))
    )
  )
)
